# spiderBoardv17-2014-12-18.net
KiCad netlist of a schematic drawn in EAGLE
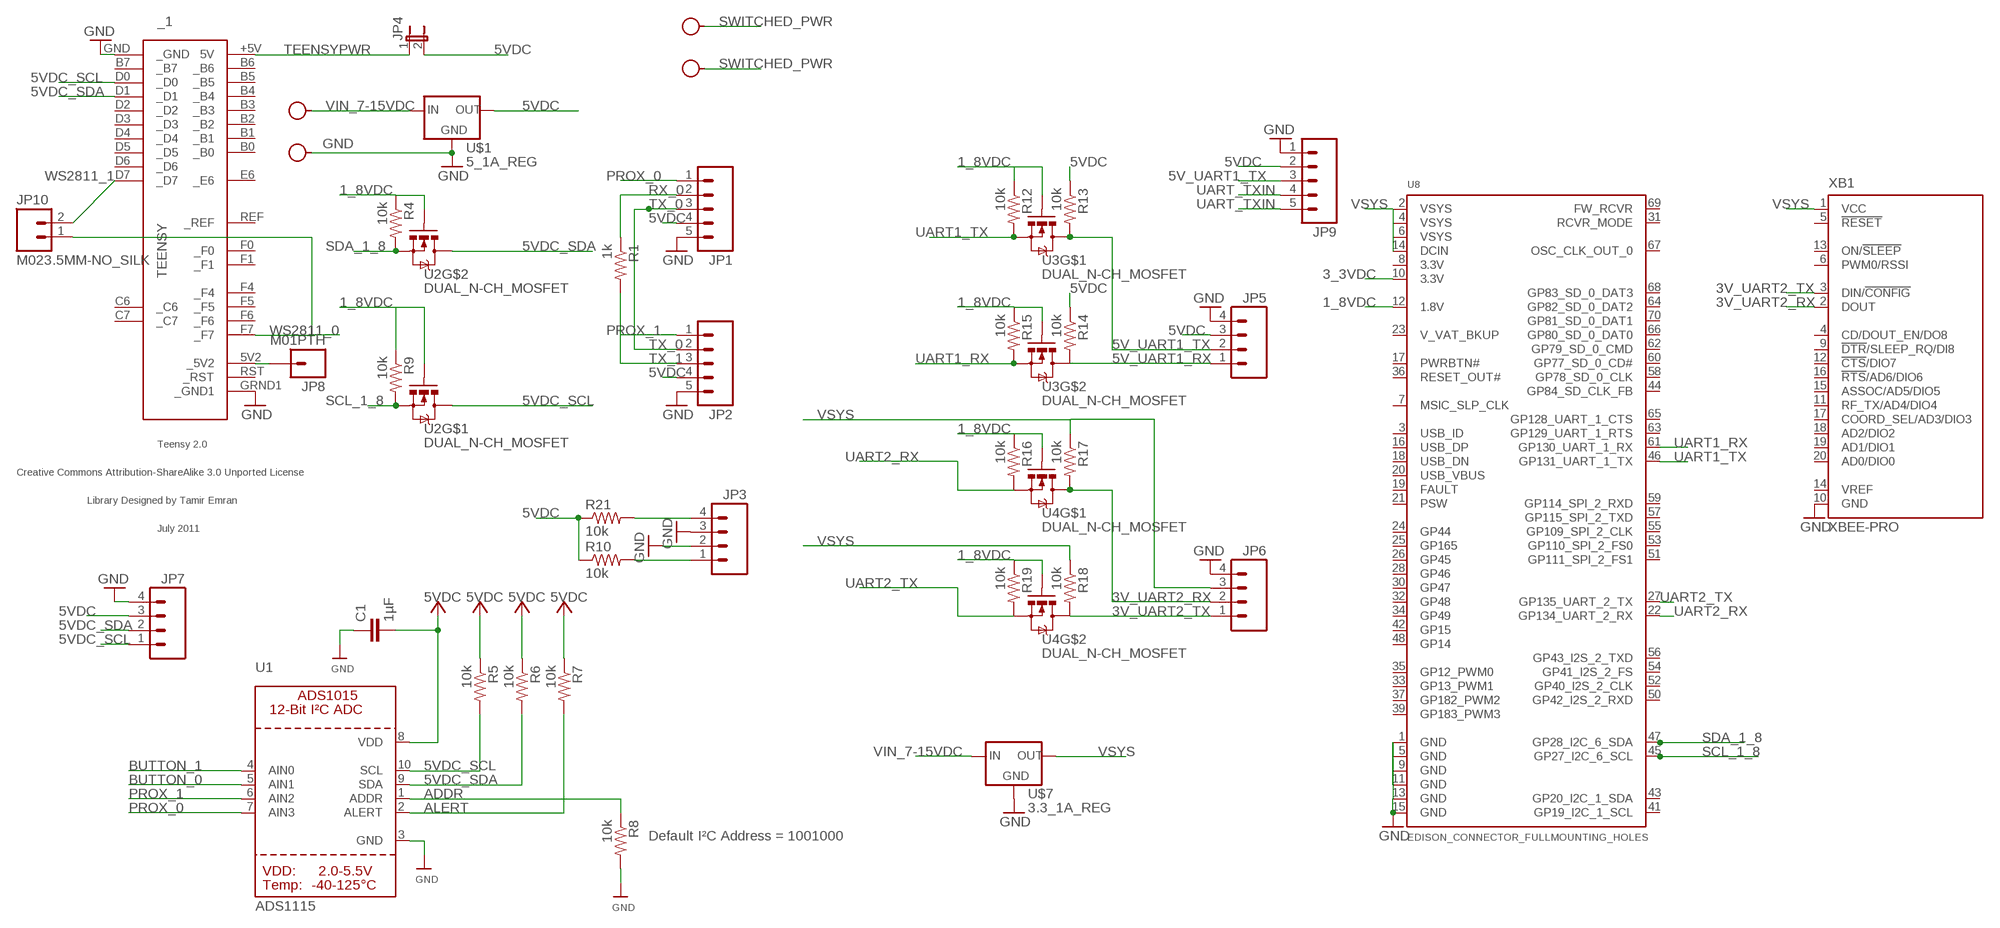
[diagram p0: schematic, sheet 1]

(export (version "E")
  (design (tool "Eeschema 10.0.6"))
  (components
    (comp (ref "C1")
      (value "1µF")
      (footprint "eagle-import:0603-CAP")
      (libsource (lib "eagle-import") (part "CAP0603-CAP"))
    )
    (comp (ref "GND")
      (value "SEW_HOLE-SMALL")
      (footprint "eagle-import:SIMPLE_HOLE_SM")
      (libsource (lib "eagle-import") (part "SEW_HOLE-SMALL"))
    )
    (comp (ref "GND15")
      (value "SEW_HOLE-SMALL")
      (footprint "eagle-import:SIMPLE_HOLE_SM")
      (libsource (lib "eagle-import") (part "SEW_HOLE-SMALL"))
    )
    (comp (ref "JP1")
      (value "M05PTH")
      (footprint "eagle-import:1X05")
      (libsource (lib "eagle-import") (part "M05PTH"))
    )
    (comp (ref "JP2")
      (value "M05PTH")
      (footprint "eagle-import:1X05")
      (libsource (lib "eagle-import") (part "M05PTH"))
    )
    (comp (ref "JP3")
      (value "M04PTH")
      (footprint "eagle-import:1X04")
      (libsource (lib "eagle-import") (part "M04PTH"))
    )
    (comp (ref "JP4")
      (value "JUMPER-2SMD-NC")
      (footprint "eagle-import:SJ_2S")
      (libsource (lib "eagle-import") (part "JUMPER-2SMD-NC"))
    )
    (comp (ref "JP5")
      (value "M04PTH")
      (footprint "eagle-import:1X04")
      (libsource (lib "eagle-import") (part "M04PTH"))
    )
    (comp (ref "JP6")
      (value "M04PTH")
      (footprint "eagle-import:1X04")
      (libsource (lib "eagle-import") (part "M04PTH"))
    )
    (comp (ref "JP7")
      (value "M04PTH")
      (footprint "eagle-import:1X04")
      (libsource (lib "eagle-import") (part "M04PTH"))
    )
    (comp (ref "JP8")
      (value "M01PTH")
      (footprint "eagle-import:1X01")
      (libsource (lib "eagle-import") (part "M01PTH"))
    )
    (comp (ref "JP9")
      (value "M05PTH")
      (footprint "eagle-import:1X05")
      (libsource (lib "eagle-import") (part "M05PTH"))
    )
    (comp (ref "JP10")
      (value "M023.5MM-NO_SILK")
      (footprint "eagle-import:SCREWTERMINAL-3.5MM-2-NS")
      (libsource (lib "eagle-import") (part "M023.5MM-NO_SILK"))
    )
    (comp (ref "R1")
      (value "1k")
      (footprint "eagle-import:0603-RES")
      (libsource (lib "eagle-import") (part "RESISTOR0603-RES"))
    )
    (comp (ref "R4")
      (value "10k")
      (footprint "eagle-import:0603-RES")
      (libsource (lib "eagle-import") (part "RESISTOR0603-RES"))
    )
    (comp (ref "R5")
      (value "10k")
      (footprint "eagle-import:0603-RES")
      (libsource (lib "eagle-import") (part "RESISTOR0603-RES"))
    )
    (comp (ref "R6")
      (value "10k")
      (footprint "eagle-import:0603-RES")
      (libsource (lib "eagle-import") (part "RESISTOR0603-RES"))
    )
    (comp (ref "R7")
      (value "10k")
      (footprint "eagle-import:0603-RES")
      (libsource (lib "eagle-import") (part "RESISTOR0603-RES"))
    )
    (comp (ref "R8")
      (value "10k")
      (footprint "eagle-import:0603-RES")
      (libsource (lib "eagle-import") (part "RESISTOR0603-RES"))
    )
    (comp (ref "R9")
      (value "10k")
      (footprint "eagle-import:0603-RES")
      (libsource (lib "eagle-import") (part "RESISTOR0603-RES"))
    )
    (comp (ref "R10")
      (value "10k")
      (footprint "eagle-import:0603-RES")
      (libsource (lib "eagle-import") (part "RESISTOR0603-RES"))
    )
    (comp (ref "R12")
      (value "10k")
      (footprint "eagle-import:0603-RES")
      (libsource (lib "eagle-import") (part "RESISTOR0603-RES"))
    )
    (comp (ref "R13")
      (value "10k")
      (footprint "eagle-import:0603-RES")
      (libsource (lib "eagle-import") (part "RESISTOR0603-RES"))
    )
    (comp (ref "R14")
      (value "10k")
      (footprint "eagle-import:0603-RES")
      (libsource (lib "eagle-import") (part "RESISTOR0603-RES"))
    )
    (comp (ref "R15")
      (value "10k")
      (footprint "eagle-import:0603-RES")
      (libsource (lib "eagle-import") (part "RESISTOR0603-RES"))
    )
    (comp (ref "R16")
      (value "10k")
      (footprint "eagle-import:0603-RES")
      (libsource (lib "eagle-import") (part "RESISTOR0603-RES"))
    )
    (comp (ref "R17")
      (value "10k")
      (footprint "eagle-import:0603-RES")
      (libsource (lib "eagle-import") (part "RESISTOR0603-RES"))
    )
    (comp (ref "R18")
      (value "10k")
      (footprint "eagle-import:0603-RES")
      (libsource (lib "eagle-import") (part "RESISTOR0603-RES"))
    )
    (comp (ref "R19")
      (value "10k")
      (footprint "eagle-import:0603-RES")
      (libsource (lib "eagle-import") (part "RESISTOR0603-RES"))
    )
    (comp (ref "R21")
      (value "10k")
      (footprint "eagle-import:0603-RES")
      (libsource (lib "eagle-import") (part "RESISTOR0603-RES"))
    )
    (comp (ref "U$1")
      (value "5_1A_REG")
      (footprint "eagle-import:1A_REG")
      (libsource (lib "eagle-import") (part "5_1A_REG"))
    )
    (comp (ref "U$7")
      (value "3.3_1A_REG")
      (footprint "eagle-import:1A_REG")
      (libsource (lib "eagle-import") (part "3.3_1A_REG"))
    )
    (comp (ref "U1")
      (value "ADS1115")
      (footprint "eagle-import:MSOP10")
      (libsource (lib "eagle-import") (part "ADC_ADS1015"))
    )
    (comp (ref "U2")
      (value "DUAL_N-CH_MOSFET")
      (footprint "eagle-import:SOT363_DUAL_N_MOSFET")
      (libsource (lib "eagle-import") (part "DUAL_N-CH_MOSFET"))
    )
    (comp (ref "U3")
      (value "DUAL_N-CH_MOSFET")
      (footprint "eagle-import:SOT363_DUAL_N_MOSFET")
      (libsource (lib "eagle-import") (part "DUAL_N-CH_MOSFET"))
    )
    (comp (ref "U4")
      (value "DUAL_N-CH_MOSFET")
      (footprint "eagle-import:SOT363_DUAL_N_MOSFET")
      (libsource (lib "eagle-import") (part "DUAL_N-CH_MOSFET"))
    )
    (comp (ref "U8")
      (value "EDISON_CONNECTOR_FULLMOUNTING_HOLES")
      (footprint "eagle-import:EDISON_DAUGHTER")
      (libsource (lib "eagle-import") (part "EDISON_CONNECTOR_FULLMOUNTING_HOLES"))
    )
    (comp (ref "VIN_7-15VDC")
      (value "SEW_HOLE-SMALL")
      (footprint "eagle-import:SIMPLE_HOLE_SM")
      (libsource (lib "eagle-import") (part "SEW_HOLE-SMALL"))
    )
    (comp (ref "VIN_7-15VDC1")
      (value "SEW_HOLE-SMALL")
      (footprint "eagle-import:SIMPLE_HOLE_SM")
      (libsource (lib "eagle-import") (part "SEW_HOLE-SMALL"))
    )
    (comp (ref "XB1")
      (value "XBEE-PRO")
      (footprint "eagle-import:XBEE-PRO")
      (fields (field (name "MPN") "XBP24-AWI-001"))
      (libsource (lib "eagle-import") (part "XBEE-PRO"))
    )
    (comp (ref "_1")
      (value "TEENSY")
      (footprint "eagle-import:TEENSY")
      (libsource (lib "eagle-import") (part "TEENSY"))
    )
  )
  (nets
    (net (code "1") (name "/1_8VDC") (class "Default")
      (node (ref "R12") (pin "1") (pinfunction "1_1") (pintype "passive"))
      (node (ref "R15") (pin "1") (pinfunction "1_1") (pintype "passive"))
      (node (ref "R16") (pin "1") (pinfunction "1_1") (pintype "passive"))
      (node (ref "R19") (pin "1") (pinfunction "1_1") (pintype "passive"))
      (node (ref "R4") (pin "1") (pinfunction "1_1") (pintype "passive"))
      (node (ref "R9") (pin "1") (pinfunction "1_1") (pintype "passive"))
      (node (ref "U2") (pin "2") (pinfunction "G_2") (pintype "passive"))
      (node (ref "U2") (pin "5") (pinfunction "G_5") (pintype "passive"))
      (node (ref "U3") (pin "2") (pinfunction "G_2") (pintype "passive"))
      (node (ref "U3") (pin "5") (pinfunction "G_5") (pintype "passive"))
      (node (ref "U4") (pin "2") (pinfunction "G_2") (pintype "passive"))
      (node (ref "U4") (pin "5") (pinfunction "G_5") (pintype "passive"))
      (node (ref "U8") (pin "12") (pinfunction "1.8V_12") (pintype "bidirectional"))
    )
    (net (code "2") (name "/3V_UART2_RX") (class "Default")
      (node (ref "JP6") (pin "2") (pinfunction "2_2") (pintype "passive"))
      (node (ref "R17") (pin "2") (pinfunction "2_2") (pintype "passive"))
      (node (ref "U4") (pin "3") (pinfunction "D_3") (pintype "passive"))
      (node (ref "XB1") (pin "2") (pinfunction "DOUT_2") (pintype "output"))
    )
    (net (code "3") (name "/3V_UART2_TX") (class "Default")
      (node (ref "JP6") (pin "1") (pinfunction "1_1") (pintype "passive"))
      (node (ref "R18") (pin "2") (pinfunction "2_2") (pintype "passive"))
      (node (ref "U4") (pin "6") (pinfunction "D_6") (pintype "passive"))
      (node (ref "XB1") (pin "3") (pinfunction "DIN/~{CONFIG}_3") (pintype "input"))
    )
    (net (code "4") (name "/3_3VDC") (class "Default")
      (node (ref "U8") (pin "10") (pinfunction "3.3V_10") (pintype "bidirectional"))
    )
    (net (code "5") (name "/5VDC_SCL") (class "Default")
      (node (ref "JP7") (pin "1") (pinfunction "1_1") (pintype "passive"))
      (node (ref "R5") (pin "2") (pinfunction "2_2") (pintype "passive"))
      (node (ref "U1") (pin "10") (pinfunction "SCL_10") (pintype "bidirectional"))
      (node (ref "U2") (pin "3") (pinfunction "D_3") (pintype "passive"))
      (node (ref "_1") (pin "D0") (pinfunction "_D0_D0") (pintype "bidirectional"))
    )
    (net (code "6") (name "/5VDC_SDA") (class "Default")
      (node (ref "JP7") (pin "2") (pinfunction "2_2") (pintype "passive"))
      (node (ref "R6") (pin "2") (pinfunction "2_2") (pintype "passive"))
      (node (ref "U1") (pin "9") (pinfunction "SDA_9") (pintype "bidirectional"))
      (node (ref "U2") (pin "6") (pinfunction "D_6") (pintype "passive"))
      (node (ref "_1") (pin "D1") (pinfunction "_D1_D1") (pintype "bidirectional"))
    )
    (net (code "7") (name "/5V_UART1_RX") (class "Default")
      (node (ref "JP5") (pin "1") (pinfunction "1_1") (pintype "passive"))
      (node (ref "R14") (pin "2") (pinfunction "2_2") (pintype "passive"))
      (node (ref "U3") (pin "6") (pinfunction "D_6") (pintype "passive"))
    )
    (net (code "8") (name "/5V_UART1_TX") (class "Default")
      (node (ref "JP5") (pin "2") (pinfunction "2_2") (pintype "passive"))
      (node (ref "JP9") (pin "3") (pinfunction "3_3") (pintype "passive"))
      (node (ref "R13") (pin "2") (pinfunction "2_2") (pintype "passive"))
      (node (ref "U3") (pin "3") (pinfunction "D_3") (pintype "passive"))
    )
    (net (code "9") (name "/ADDR") (class "Default")
      (node (ref "R8") (pin "1") (pinfunction "1_1") (pintype "passive"))
      (node (ref "U1") (pin "1") (pinfunction "ADDR_1") (pintype "bidirectional"))
    )
    (net (code "10") (name "/ALERT") (class "Default")
      (node (ref "R7") (pin "2") (pinfunction "2_2") (pintype "passive"))
      (node (ref "U1") (pin "2") (pinfunction "ALERT_2") (pintype "bidirectional"))
    )
    (net (code "11") (name "/BUTTON_0") (class "Default")
      (node (ref "JP3") (pin "4") (pinfunction "4_4") (pintype "passive"))
      (node (ref "R21") (pin "2") (pinfunction "2_2") (pintype "passive"))
      (node (ref "U1") (pin "5") (pinfunction "AIN1_5") (pintype "bidirectional"))
    )
    (net (code "12") (name "/BUTTON_1") (class "Default")
      (node (ref "JP3") (pin "1") (pinfunction "1_1") (pintype "passive"))
      (node (ref "R10") (pin "2") (pinfunction "2_2") (pintype "passive"))
      (node (ref "U1") (pin "4") (pinfunction "AIN0_4") (pintype "bidirectional"))
    )
    (net (code "13") (name "/PROX_0") (class "Default")
      (node (ref "JP1") (pin "1") (pinfunction "1_1") (pintype "passive"))
      (node (ref "U1") (pin "7") (pinfunction "AIN3_7") (pintype "bidirectional"))
    )
    (net (code "14") (name "/PROX_1") (class "Default")
      (node (ref "JP2") (pin "1") (pinfunction "1_1") (pintype "passive"))
      (node (ref "U1") (pin "6") (pinfunction "AIN2_6") (pintype "bidirectional"))
    )
    (net (code "15") (name "/RX_0") (class "Default")
      (node (ref "JP1") (pin "2") (pinfunction "2_2") (pintype "passive"))
      (node (ref "R1") (pin "1") (pinfunction "1_1") (pintype "passive"))
    )
    (net (code "16") (name "/SCL_1_8") (class "Default")
      (node (ref "R9") (pin "2") (pinfunction "2_2") (pintype "passive"))
      (node (ref "U2") (pin "4") (pinfunction "S_4") (pintype "passive"))
      (node (ref "U8") (pin "45") (pinfunction "GP27_I2C_6_SCL_45") (pintype "bidirectional"))
    )
    (net (code "17") (name "/SDA_1_8") (class "Default")
      (node (ref "R4") (pin "2") (pinfunction "2_2") (pintype "passive"))
      (node (ref "U2") (pin "1") (pinfunction "S_1") (pintype "passive"))
      (node (ref "U8") (pin "47") (pinfunction "GP28_I2C_6_SDA_47") (pintype "bidirectional"))
    )
    (net (code "18") (name "/SWITCHED_PWR") (class "Default")
      (node (ref "GND15") (pin "P$1") (pinfunction "P$1_P$1") (pintype "bidirectional"))
      (node (ref "VIN_7-15VDC1") (pin "P$1") (pinfunction "P$1_P$1") (pintype "bidirectional"))
    )
    (net (code "19") (name "/TEENSYPWR") (class "Default")
      (node (ref "JP4") (pin "1") (pinfunction "1_1") (pintype "passive"))
      (node (ref "JP8") (pin "1") (pinfunction "1_1") (pintype "passive"))
      (node (ref "_1") (pin "+5V") (pinfunction "5V_+5V") (pintype "bidirectional"))
      (node (ref "_1") (pin "5V2") (pinfunction "_5V2_5V2") (pintype "bidirectional"))
    )
    (net (code "20") (name "/TX_0") (class "Default")
      (node (ref "JP1") (pin "3") (pinfunction "3_3") (pintype "passive"))
      (node (ref "JP2") (pin "2") (pinfunction "2_2") (pintype "passive"))
    )
    (net (code "21") (name "/TX_1") (class "Default")
      (node (ref "JP2") (pin "3") (pinfunction "3_3") (pintype "passive"))
      (node (ref "R1") (pin "2") (pinfunction "2_2") (pintype "passive"))
    )
    (net (code "22") (name "/UART1_RX") (class "Default")
      (node (ref "R15") (pin "2") (pinfunction "2_2") (pintype "passive"))
      (node (ref "U3") (pin "1") (pinfunction "S_1") (pintype "passive"))
      (node (ref "U8") (pin "61") (pinfunction "GP130_UART_1_RX_61") (pintype "bidirectional"))
    )
    (net (code "23") (name "/UART1_TX") (class "Default")
      (node (ref "R12") (pin "2") (pinfunction "2_2") (pintype "passive"))
      (node (ref "U3") (pin "4") (pinfunction "S_4") (pintype "passive"))
      (node (ref "U8") (pin "46") (pinfunction "GP131_UART_1_TX_46") (pintype "bidirectional"))
    )
    (net (code "24") (name "/UART2_RX") (class "Default")
      (node (ref "R16") (pin "2") (pinfunction "2_2") (pintype "passive"))
      (node (ref "U4") (pin "4") (pinfunction "S_4") (pintype "passive"))
      (node (ref "U8") (pin "22") (pinfunction "GP134_UART_2_RX_22") (pintype "bidirectional"))
    )
    (net (code "25") (name "/UART2_TX") (class "Default")
      (node (ref "R19") (pin "2") (pinfunction "2_2") (pintype "passive"))
      (node (ref "U4") (pin "1") (pinfunction "S_1") (pintype "passive"))
      (node (ref "U8") (pin "27") (pinfunction "GP135_UART_2_TX_27") (pintype "bidirectional"))
    )
    (net (code "26") (name "/UART_TXIN") (class "Default")
      (node (ref "JP9") (pin "4") (pinfunction "4_4") (pintype "passive"))
      (node (ref "JP9") (pin "5") (pinfunction "5_5") (pintype "passive"))
    )
    (net (code "27") (name "/VIN_7-15VDC") (class "Default")
      (node (ref "U$1") (pin "IN") (pinfunction "IN_IN") (pintype "input"))
      (node (ref "U$7") (pin "IN") (pinfunction "IN_IN") (pintype "input"))
      (node (ref "VIN_7-15VDC") (pin "P$1") (pinfunction "P$1_P$1") (pintype "bidirectional"))
    )
    (net (code "28") (name "/VSYS") (class "Default")
      (node (ref "JP6") (pin "3") (pinfunction "3_3") (pintype "passive"))
      (node (ref "R17") (pin "1") (pinfunction "1_1") (pintype "passive"))
      (node (ref "R18") (pin "1") (pinfunction "1_1") (pintype "passive"))
      (node (ref "U$7") (pin "OUT") (pinfunction "OUT_OUT") (pintype "output"))
      (node (ref "U8") (pin "14") (pinfunction "DCIN_14") (pintype "bidirectional"))
      (node (ref "U8") (pin "2") (pinfunction "VSYS_2") (pintype "bidirectional"))
      (node (ref "U8") (pin "4") (pinfunction "VSYS_4") (pintype "bidirectional"))
      (node (ref "U8") (pin "6") (pinfunction "VSYS_6") (pintype "bidirectional"))
      (node (ref "XB1") (pin "1") (pinfunction "VCC_1") (pintype "power_in"))
    )
    (net (code "29") (name "/WS2811_0") (class "Default")
      (node (ref "JP10") (pin "1") (pinfunction "1_1") (pintype "passive"))
      (node (ref "_1") (pin "F7") (pinfunction "_F7_F7") (pintype "bidirectional"))
    )
    (net (code "30") (name "/WS2811_1") (class "Default")
      (node (ref "JP10") (pin "2") (pinfunction "2_2") (pintype "passive"))
      (node (ref "_1") (pin "D7") (pinfunction "_D7_D7") (pintype "bidirectional"))
    )
    (net (code "31") (name "GND") (class "Default")
      (node (ref "C1") (pin "1") (pinfunction "1_1") (pintype "passive"))
      (node (ref "GND") (pin "P$1") (pinfunction "P$1_P$1") (pintype "bidirectional"))
      (node (ref "JP1") (pin "5") (pinfunction "5_5") (pintype "passive"))
      (node (ref "JP2") (pin "5") (pinfunction "5_5") (pintype "passive"))
      (node (ref "JP3") (pin "2") (pinfunction "2_2") (pintype "passive"))
      (node (ref "JP3") (pin "3") (pinfunction "3_3") (pintype "passive"))
      (node (ref "JP5") (pin "4") (pinfunction "4_4") (pintype "passive"))
      (node (ref "JP6") (pin "4") (pinfunction "4_4") (pintype "passive"))
      (node (ref "JP7") (pin "4") (pinfunction "4_4") (pintype "passive"))
      (node (ref "JP9") (pin "1") (pinfunction "1_1") (pintype "passive"))
      (node (ref "R8") (pin "2") (pinfunction "2_2") (pintype "passive"))
      (node (ref "U$1") (pin "GND") (pinfunction "GND_GND") (pintype "input"))
      (node (ref "U$7") (pin "GND") (pinfunction "GND_GND") (pintype "input"))
      (node (ref "U1") (pin "3") (pinfunction "GND_3") (pintype "bidirectional"))
      (node (ref "U8") (pin "1") (pinfunction "GND_1") (pintype "bidirectional"))
      (node (ref "U8") (pin "11") (pinfunction "GND_11") (pintype "bidirectional"))
      (node (ref "U8") (pin "13") (pinfunction "GND_13") (pintype "bidirectional"))
      (node (ref "U8") (pin "15") (pinfunction "GND_15") (pintype "bidirectional"))
      (node (ref "U8") (pin "5") (pinfunction "GND_5") (pintype "bidirectional"))
      (node (ref "U8") (pin "9") (pinfunction "GND_9") (pintype "bidirectional"))
      (node (ref "XB1") (pin "10") (pinfunction "GND_10") (pintype "power_in"))
      (node (ref "_1") (pin "GND") (pinfunction "_GND_GND") (pintype "bidirectional"))
      (node (ref "_1") (pin "GRND1") (pinfunction "_GND1_GRND1") (pintype "bidirectional"))
    )
    (net (code "32") (name "VDD") (class "Default")
      (node (ref "C1") (pin "2") (pinfunction "2_2") (pintype "passive"))
      (node (ref "JP1") (pin "4") (pinfunction "4_4") (pintype "passive"))
      (node (ref "JP2") (pin "4") (pinfunction "4_4") (pintype "passive"))
      (node (ref "JP4") (pin "2") (pinfunction "2_2") (pintype "passive"))
      (node (ref "JP5") (pin "3") (pinfunction "3_3") (pintype "passive"))
      (node (ref "JP7") (pin "3") (pinfunction "3_3") (pintype "passive"))
      (node (ref "JP9") (pin "2") (pinfunction "2_2") (pintype "passive"))
      (node (ref "R10") (pin "1") (pinfunction "1_1") (pintype "passive"))
      (node (ref "R13") (pin "1") (pinfunction "1_1") (pintype "passive"))
      (node (ref "R14") (pin "1") (pinfunction "1_1") (pintype "passive"))
      (node (ref "R21") (pin "1") (pinfunction "1_1") (pintype "passive"))
      (node (ref "R5") (pin "1") (pinfunction "1_1") (pintype "passive"))
      (node (ref "R6") (pin "1") (pinfunction "1_1") (pintype "passive"))
      (node (ref "R7") (pin "1") (pinfunction "1_1") (pintype "passive"))
      (node (ref "U$1") (pin "OUT") (pinfunction "OUT_OUT") (pintype "output"))
      (node (ref "U1") (pin "8") (pinfunction "VDD_8") (pintype "bidirectional"))
    )
    (net (code "33") (name "unconnected-(U8-3.3V-Pad8)") (class "Default")
      (node (ref "U8") (pin "8") (pinfunction "3.3V_8") (pintype "bidirectional"))
    )
    (net (code "34") (name "unconnected-(U8-FAULT-Pad19)") (class "Default")
      (node (ref "U8") (pin "19") (pinfunction "FAULT_19") (pintype "bidirectional"))
    )
    (net (code "35") (name "unconnected-(U8-FW_RCVR-Pad69)") (class "Default")
      (node (ref "U8") (pin "69") (pinfunction "FW_RCVR_69") (pintype "bidirectional"))
    )
    (net (code "36") (name "unconnected-(U8-GP12_PWM0-Pad35)") (class "Default")
      (node (ref "U8") (pin "35") (pinfunction "GP12_PWM0_35") (pintype "bidirectional"))
    )
    (net (code "37") (name "unconnected-(U8-GP13_PWM1-Pad33)") (class "Default")
      (node (ref "U8") (pin "33") (pinfunction "GP13_PWM1_33") (pintype "bidirectional"))
    )
    (net (code "38") (name "unconnected-(U8-GP14-Pad48)") (class "Default")
      (node (ref "U8") (pin "48") (pinfunction "GP14_48") (pintype "bidirectional"))
    )
    (net (code "39") (name "unconnected-(U8-GP15-Pad42)") (class "Default")
      (node (ref "U8") (pin "42") (pinfunction "GP15_42") (pintype "bidirectional"))
    )
    (net (code "40") (name "unconnected-(U8-GP19_I2C_1_SCL-Pad41)") (class "Default")
      (node (ref "U8") (pin "41") (pinfunction "GP19_I2C_1_SCL_41") (pintype "bidirectional"))
    )
    (net (code "41") (name "unconnected-(U8-GP20_I2C_1_SDA-Pad43)") (class "Default")
      (node (ref "U8") (pin "43") (pinfunction "GP20_I2C_1_SDA_43") (pintype "bidirectional"))
    )
    (net (code "42") (name "unconnected-(U8-GP40_I2S_2_CLK-Pad52)") (class "Default")
      (node (ref "U8") (pin "52") (pinfunction "GP40_I2S_2_CLK_52") (pintype "bidirectional"))
    )
    (net (code "43") (name "unconnected-(U8-GP41_I2S_2_FS-Pad54)") (class "Default")
      (node (ref "U8") (pin "54") (pinfunction "GP41_I2S_2_FS_54") (pintype "bidirectional"))
    )
    (net (code "44") (name "unconnected-(U8-GP42_I2S_2_RXD-Pad50)") (class "Default")
      (node (ref "U8") (pin "50") (pinfunction "GP42_I2S_2_RXD_50") (pintype "bidirectional"))
    )
    (net (code "45") (name "unconnected-(U8-GP43_I2S_2_TXD-Pad56)") (class "Default")
      (node (ref "U8") (pin "56") (pinfunction "GP43_I2S_2_TXD_56") (pintype "bidirectional"))
    )
    (net (code "46") (name "unconnected-(U8-GP44-Pad24)") (class "Default")
      (node (ref "U8") (pin "24") (pinfunction "GP44_24") (pintype "bidirectional"))
    )
    (net (code "47") (name "unconnected-(U8-GP45-Pad26)") (class "Default")
      (node (ref "U8") (pin "26") (pinfunction "GP45_26") (pintype "bidirectional"))
    )
    (net (code "48") (name "unconnected-(U8-GP46-Pad28)") (class "Default")
      (node (ref "U8") (pin "28") (pinfunction "GP46_28") (pintype "bidirectional"))
    )
    (net (code "49") (name "unconnected-(U8-GP47-Pad30)") (class "Default")
      (node (ref "U8") (pin "30") (pinfunction "GP47_30") (pintype "bidirectional"))
    )
    (net (code "50") (name "unconnected-(U8-GP48-Pad32)") (class "Default")
      (node (ref "U8") (pin "32") (pinfunction "GP48_32") (pintype "bidirectional"))
    )
    (net (code "51") (name "unconnected-(U8-GP49-Pad34)") (class "Default")
      (node (ref "U8") (pin "34") (pinfunction "GP49_34") (pintype "bidirectional"))
    )
    (net (code "52") (name "unconnected-(U8-GP77_SD_0_CD#-Pad60)") (class "Default")
      (node (ref "U8") (pin "60") (pinfunction "GP77_SD_0_CD#_60") (pintype "bidirectional"))
    )
    (net (code "53") (name "unconnected-(U8-GP78_SD_0_CLK-Pad58)") (class "Default")
      (node (ref "U8") (pin "58") (pinfunction "GP78_SD_0_CLK_58") (pintype "bidirectional"))
    )
    (net (code "54") (name "unconnected-(U8-GP79_SD_0_CMD-Pad62)") (class "Default")
      (node (ref "U8") (pin "62") (pinfunction "GP79_SD_0_CMD_62") (pintype "bidirectional"))
    )
    (net (code "55") (name "unconnected-(U8-GP80_SD_0_DAT0-Pad66)") (class "Default")
      (node (ref "U8") (pin "66") (pinfunction "GP80_SD_0_DAT0_66") (pintype "bidirectional"))
    )
    (net (code "56") (name "unconnected-(U8-GP81_SD_0_DAT1-Pad70)") (class "Default")
      (node (ref "U8") (pin "70") (pinfunction "GP81_SD_0_DAT1_70") (pintype "bidirectional"))
    )
    (net (code "57") (name "unconnected-(U8-GP82_SD_0_DAT2-Pad64)") (class "Default")
      (node (ref "U8") (pin "64") (pinfunction "GP82_SD_0_DAT2_64") (pintype "bidirectional"))
    )
    (net (code "58") (name "unconnected-(U8-GP83_SD_0_DAT3-Pad68)") (class "Default")
      (node (ref "U8") (pin "68") (pinfunction "GP83_SD_0_DAT3_68") (pintype "bidirectional"))
    )
    (net (code "59") (name "unconnected-(U8-GP84_SD_CLK_FB-Pad44)") (class "Default")
      (node (ref "U8") (pin "44") (pinfunction "GP84_SD_CLK_FB_44") (pintype "bidirectional"))
    )
    (net (code "60") (name "unconnected-(U8-GP109_SPI_2_CLK-Pad55)") (class "Default")
      (node (ref "U8") (pin "55") (pinfunction "GP109_SPI_2_CLK_55") (pintype "bidirectional"))
    )
    (net (code "61") (name "unconnected-(U8-GP110_SPI_2_FS0-Pad53)") (class "Default")
      (node (ref "U8") (pin "53") (pinfunction "GP110_SPI_2_FS0_53") (pintype "bidirectional"))
    )
    (net (code "62") (name "unconnected-(U8-GP111_SPI_2_FS1-Pad51)") (class "Default")
      (node (ref "U8") (pin "51") (pinfunction "GP111_SPI_2_FS1_51") (pintype "bidirectional"))
    )
    (net (code "63") (name "unconnected-(U8-GP114_SPI_2_RXD-Pad59)") (class "Default")
      (node (ref "U8") (pin "59") (pinfunction "GP114_SPI_2_RXD_59") (pintype "bidirectional"))
    )
    (net (code "64") (name "unconnected-(U8-GP115_SPI_2_TXD-Pad57)") (class "Default")
      (node (ref "U8") (pin "57") (pinfunction "GP115_SPI_2_TXD_57") (pintype "bidirectional"))
    )
    (net (code "65") (name "unconnected-(U8-GP128_UART_1_CTS-Pad65)") (class "Default")
      (node (ref "U8") (pin "65") (pinfunction "GP128_UART_1_CTS_65") (pintype "bidirectional"))
    )
    (net (code "66") (name "unconnected-(U8-GP129_UART_1_RTS-Pad63)") (class "Default")
      (node (ref "U8") (pin "63") (pinfunction "GP129_UART_1_RTS_63") (pintype "bidirectional"))
    )
    (net (code "67") (name "unconnected-(U8-GP165-Pad25)") (class "Default")
      (node (ref "U8") (pin "25") (pinfunction "GP165_25") (pintype "bidirectional"))
    )
    (net (code "68") (name "unconnected-(U8-GP182_PWM2-Pad37)") (class "Default")
      (node (ref "U8") (pin "37") (pinfunction "GP182_PWM2_37") (pintype "bidirectional"))
    )
    (net (code "69") (name "unconnected-(U8-GP183_PWM3-Pad39)") (class "Default")
      (node (ref "U8") (pin "39") (pinfunction "GP183_PWM3_39") (pintype "bidirectional"))
    )
    (net (code "70") (name "unconnected-(U8-MSIC_SLP_CLK-Pad7)") (class "Default")
      (node (ref "U8") (pin "7") (pinfunction "MSIC_SLP_CLK_7") (pintype "bidirectional"))
    )
    (net (code "71") (name "unconnected-(U8-OSC_CLK_OUT_0-Pad67)") (class "Default")
      (node (ref "U8") (pin "67") (pinfunction "OSC_CLK_OUT_0_67") (pintype "bidirectional"))
    )
    (net (code "72") (name "unconnected-(U8-PSW-Pad21)") (class "Default")
      (node (ref "U8") (pin "21") (pinfunction "PSW_21") (pintype "bidirectional"))
    )
    (net (code "73") (name "unconnected-(U8-PWRBTN#-Pad17)") (class "Default")
      (node (ref "U8") (pin "17") (pinfunction "PWRBTN#_17") (pintype "bidirectional"))
    )
    (net (code "74") (name "unconnected-(U8-RCVR_MODE-Pad31)") (class "Default")
      (node (ref "U8") (pin "31") (pinfunction "RCVR_MODE_31") (pintype "bidirectional"))
    )
    (net (code "75") (name "unconnected-(U8-RESET_OUT#-Pad36)") (class "Default")
      (node (ref "U8") (pin "36") (pinfunction "RESET_OUT#_36") (pintype "bidirectional"))
    )
    (net (code "76") (name "unconnected-(U8-USB_DN-Pad18)") (class "Default")
      (node (ref "U8") (pin "18") (pinfunction "USB_DN_18") (pintype "bidirectional"))
    )
    (net (code "77") (name "unconnected-(U8-USB_DP-Pad16)") (class "Default")
      (node (ref "U8") (pin "16") (pinfunction "USB_DP_16") (pintype "bidirectional"))
    )
    (net (code "78") (name "unconnected-(U8-USB_ID-Pad3)") (class "Default")
      (node (ref "U8") (pin "3") (pinfunction "USB_ID_3") (pintype "bidirectional"))
    )
    (net (code "79") (name "unconnected-(U8-USB_VBUS-Pad20)") (class "Default")
      (node (ref "U8") (pin "20") (pinfunction "USB_VBUS_20") (pintype "bidirectional"))
    )
    (net (code "80") (name "unconnected-(U8-V_VAT_BKUP-Pad23)") (class "Default")
      (node (ref "U8") (pin "23") (pinfunction "V_VAT_BKUP_23") (pintype "bidirectional"))
    )
    (net (code "81") (name "unconnected-(XB1-AD0{slash}DIO0-Pad20)") (class "Default")
      (node (ref "XB1") (pin "20") (pinfunction "AD0/DIO0_20") (pintype "bidirectional"))
    )
    (net (code "82") (name "unconnected-(XB1-AD1{slash}DIO1-Pad19)") (class "Default")
      (node (ref "XB1") (pin "19") (pinfunction "AD1/DIO1_19") (pintype "bidirectional"))
    )
    (net (code "83") (name "unconnected-(XB1-AD2{slash}DIO2-Pad18)") (class "Default")
      (node (ref "XB1") (pin "18") (pinfunction "AD2/DIO2_18") (pintype "bidirectional"))
    )
    (net (code "84") (name "unconnected-(XB1-ASSOC{slash}AD5{slash}DIO5-Pad15)") (class "Default")
      (node (ref "XB1") (pin "15") (pinfunction "ASSOC/AD5/DIO5_15") (pintype "bidirectional"))
    )
    (net (code "85") (name "unconnected-(XB1-CD{slash}DOUT_EN{slash}DO8-Pad4)") (class "Default")
      (node (ref "XB1") (pin "4") (pinfunction "CD/DOUT_EN/DO8_4") (pintype "output"))
    )
    (net (code "86") (name "unconnected-(XB1-COORD_SEL{slash}AD3{slash}DIO3-Pad17)") (class "Default")
      (node (ref "XB1") (pin "17") (pinfunction "COORD_SEL/AD3/DIO3_17") (pintype "bidirectional"))
    )
    (net (code "87") (name "unconnected-(XB1-ON{slash}~{SLEEP}-Pad13)") (class "Default")
      (node (ref "XB1") (pin "13") (pinfunction "ON/~{SLEEP}_13") (pintype "output"))
    )
    (net (code "88") (name "unconnected-(XB1-PWM0{slash}RSSI-Pad6)") (class "Default")
      (node (ref "XB1") (pin "6") (pinfunction "PWM0/RSSI_6") (pintype "output"))
    )
    (net (code "89") (name "unconnected-(XB1-RF_TX{slash}AD4{slash}DIO4-Pad11)") (class "Default")
      (node (ref "XB1") (pin "11") (pinfunction "RF_TX/AD4/DIO4_11") (pintype "bidirectional"))
    )
    (net (code "90") (name "unconnected-(XB1-VREF-Pad14)") (class "Default")
      (node (ref "XB1") (pin "14") (pinfunction "VREF_14") (pintype "input"))
    )
    (net (code "91") (name "unconnected-(XB1-~{CTS}{slash}DIO7-Pad12)") (class "Default")
      (node (ref "XB1") (pin "12") (pinfunction "~{CTS}/DIO7_12") (pintype "bidirectional"))
    )
    (net (code "92") (name "unconnected-(XB1-~{DTR}{slash}SLEEP_RQ{slash}DI8-Pad9)") (class "Default")
      (node (ref "XB1") (pin "9") (pinfunction "~{DTR}/SLEEP_RQ/DI8_9") (pintype "bidirectional"))
    )
    (net (code "93") (name "unconnected-(XB1-~{RESET}-Pad5)") (class "Default")
      (node (ref "XB1") (pin "5") (pinfunction "~{RESET}_5") (pintype "input"))
    )
    (net (code "94") (name "unconnected-(XB1-~{RTS}{slash}AD6{slash}DIO6-Pad16)") (class "Default")
      (node (ref "XB1") (pin "16") (pinfunction "~{RTS}/AD6/DIO6_16") (pintype "bidirectional"))
    )
    (net (code "95") (name "unconnected-(_1-_B0-PadB0)") (class "Default")
      (node (ref "_1") (pin "B0") (pinfunction "_B0_B0") (pintype "bidirectional"))
    )
    (net (code "96") (name "unconnected-(_1-_B1-PadB1)") (class "Default")
      (node (ref "_1") (pin "B1") (pinfunction "_B1_B1") (pintype "bidirectional"))
    )
    (net (code "97") (name "unconnected-(_1-_B2-PadB2)") (class "Default")
      (node (ref "_1") (pin "B2") (pinfunction "_B2_B2") (pintype "bidirectional"))
    )
    (net (code "98") (name "unconnected-(_1-_B3-PadB3)") (class "Default")
      (node (ref "_1") (pin "B3") (pinfunction "_B3_B3") (pintype "bidirectional"))
    )
    (net (code "99") (name "unconnected-(_1-_B4-PadB4)") (class "Default")
      (node (ref "_1") (pin "B4") (pinfunction "_B4_B4") (pintype "bidirectional"))
    )
    (net (code "100") (name "unconnected-(_1-_B5-PadB5)") (class "Default")
      (node (ref "_1") (pin "B5") (pinfunction "_B5_B5") (pintype "bidirectional"))
    )
    (net (code "101") (name "unconnected-(_1-_B6-PadB6)") (class "Default")
      (node (ref "_1") (pin "B6") (pinfunction "_B6_B6") (pintype "bidirectional"))
    )
    (net (code "102") (name "unconnected-(_1-_B7-PadB7)") (class "Default")
      (node (ref "_1") (pin "B7") (pinfunction "_B7_B7") (pintype "bidirectional"))
    )
    (net (code "103") (name "unconnected-(_1-_C6-PadC6)") (class "Default")
      (node (ref "_1") (pin "C6") (pinfunction "_C6_C6") (pintype "bidirectional"))
    )
    (net (code "104") (name "unconnected-(_1-_C7-PadC7)") (class "Default")
      (node (ref "_1") (pin "C7") (pinfunction "_C7_C7") (pintype "bidirectional"))
    )
    (net (code "105") (name "unconnected-(_1-_D2-PadD2)") (class "Default")
      (node (ref "_1") (pin "D2") (pinfunction "_D2_D2") (pintype "bidirectional"))
    )
    (net (code "106") (name "unconnected-(_1-_D3-PadD3)") (class "Default")
      (node (ref "_1") (pin "D3") (pinfunction "_D3_D3") (pintype "bidirectional"))
    )
    (net (code "107") (name "unconnected-(_1-_D4-PadD4)") (class "Default")
      (node (ref "_1") (pin "D4") (pinfunction "_D4_D4") (pintype "bidirectional"))
    )
    (net (code "108") (name "unconnected-(_1-_D5-PadD5)") (class "Default")
      (node (ref "_1") (pin "D5") (pinfunction "_D5_D5") (pintype "bidirectional"))
    )
    (net (code "109") (name "unconnected-(_1-_D6-PadD6)") (class "Default")
      (node (ref "_1") (pin "D6") (pinfunction "_D6_D6") (pintype "bidirectional"))
    )
    (net (code "110") (name "unconnected-(_1-_E6-PadE6)") (class "Default")
      (node (ref "_1") (pin "E6") (pinfunction "_E6_E6") (pintype "bidirectional"))
    )
    (net (code "111") (name "unconnected-(_1-_F0-PadF0)") (class "Default")
      (node (ref "_1") (pin "F0") (pinfunction "_F0_F0") (pintype "bidirectional"))
    )
    (net (code "112") (name "unconnected-(_1-_F1-PadF1)") (class "Default")
      (node (ref "_1") (pin "F1") (pinfunction "_F1_F1") (pintype "bidirectional"))
    )
    (net (code "113") (name "unconnected-(_1-_F4-PadF4)") (class "Default")
      (node (ref "_1") (pin "F4") (pinfunction "_F4_F4") (pintype "bidirectional"))
    )
    (net (code "114") (name "unconnected-(_1-_F5-PadF5)") (class "Default")
      (node (ref "_1") (pin "F5") (pinfunction "_F5_F5") (pintype "bidirectional"))
    )
    (net (code "115") (name "unconnected-(_1-_F6-PadF6)") (class "Default")
      (node (ref "_1") (pin "F6") (pinfunction "_F6_F6") (pintype "bidirectional"))
    )
    (net (code "116") (name "unconnected-(_1-_REF-PadREF)") (class "Default")
      (node (ref "_1") (pin "REF") (pinfunction "_REF_REF") (pintype "bidirectional"))
    )
    (net (code "117") (name "unconnected-(_1-_RST-PadRST)") (class "Default")
      (node (ref "_1") (pin "RST") (pinfunction "_RST_RST") (pintype "bidirectional"))
    )
  )
)
